# pulsegen.net
KiCad netlist of a schematic drawn in Altium Designer
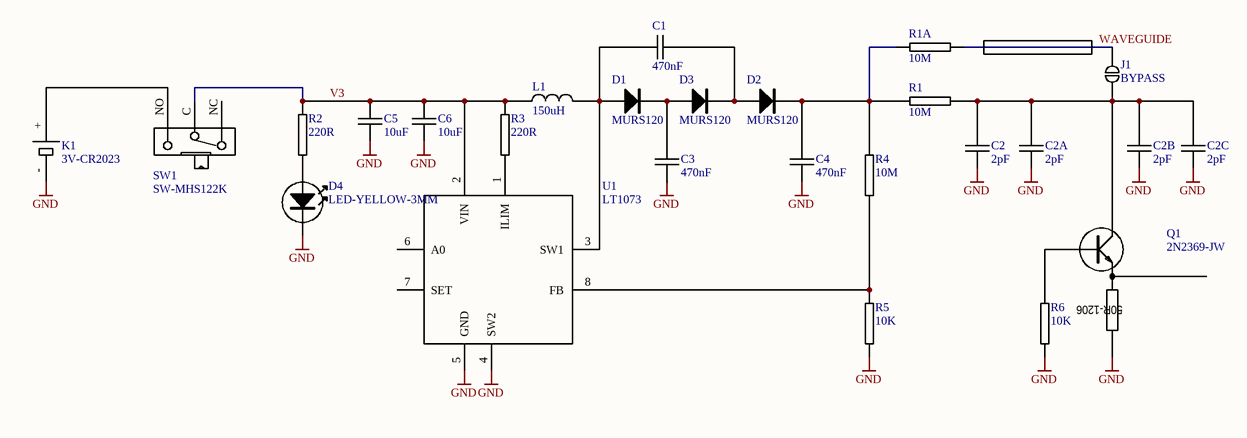
[diagram p0: pulsegen.SchDoc]

(export (version "E")
  (design (tool "Eeschema 10.0.6"))
  (components
    (comp (ref "C1")
      (value "470nF")
      (footprint "1812C-GENERIC")
      (description "CAPACITOR 1812 CERAMIC")
      (libsource (lib "SMD Capacitors Other") (part "1812C-470nF-250V-X7R-MUR"))
    )
    (comp (ref "C2")
      (value "2pF")
      (footprint "0805C-GENERIC")
      (description "CAP 10UF 6.3V CERAMIC X5R 0805")
      (fields (field (name "TOLERANCE") "±20%"))
      (libsource (lib "vh_Altium Library") (part "0805C-10UF-6V3-X5R-PAN"))
    )
    (comp (ref "C2A")
      (value "2pF")
      (footprint "0805C-GENERIC")
      (description "CAP 10UF 6.3V CERAMIC X5R 0805")
      (fields (field (name "TOLERANCE") "±20%"))
      (libsource (lib "vh_Altium Library") (part "0805C-10UF-6V3-X5R-PAN"))
    )
    (comp (ref "C2B")
      (value "2pF")
      (footprint "0805C-GENERIC")
      (description "CAP 10UF 6.3V CERAMIC X5R 0805")
      (fields (field (name "TOLERANCE") "±20%"))
      (libsource (lib "vh_Altium Library") (part "0805C-10UF-6V3-X5R-PAN"))
    )
    (comp (ref "C2C")
      (value "2pF")
      (footprint "0805C-GENERIC")
      (description "CAP 10UF 6.3V CERAMIC X5R 0805")
      (fields (field (name "TOLERANCE") "±20%"))
      (libsource (lib "vh_Altium Library") (part "0805C-10UF-6V3-X5R-PAN"))
    )
    (comp (ref "C3")
      (value "470nF")
      (footprint "1812C-GENERIC")
      (description "CAPACITOR 1812 CERAMIC")
      (libsource (lib "SMD Capacitors Other") (part "1812C-470nF-250V-X7R-MUR"))
    )
    (comp (ref "C4")
      (value "470nF")
      (footprint "1812C-GENERIC")
      (description "CAPACITOR 1812 CERAMIC")
      (libsource (lib "SMD Capacitors Other") (part "1812C-470nF-250V-X7R-MUR"))
    )
    (comp (ref "C5")
      (value "10uF")
      (footprint "0805C-GENERIC")
      (description "CAP 10UF 6.3V CERAMIC X5R 0805")
      (fields (field (name "TOLERANCE") "±20%"))
      (libsource (lib "vh_Altium Library") (part "0805C-10UF-6V3-X5R-PAN"))
    )
    (comp (ref "C6")
      (value "10uF")
      (footprint "0805C-GENERIC")
      (description "CAP 10UF 6.3V CERAMIC X5R 0805")
      (fields (field (name "TOLERANCE") "±20%"))
      (libsource (lib "vh_Altium Library") (part "0805C-10UF-6V3-X5R-PAN"))
    )
    (comp (ref "D1")
      (value "MURS120")
      (footprint "DIODE-SMB")
      (description "DIODE")
      (libsource (lib "SMD Diodes") (part "MURS120"))
    )
    (comp (ref "D2")
      (value "MURS120")
      (footprint "DIODE-SMB")
      (description "DIODE")
      (libsource (lib "SMD Diodes") (part "MURS120"))
    )
    (comp (ref "D3")
      (value "MURS120")
      (footprint "DIODE-SMB")
      (description "DIODE")
      (libsource (lib "SMD Diodes") (part "MURS120"))
    )
    (comp (ref "D4")
      (value "LED-YELLOW-3MM")
      (footprint "LED-3MM-YELLOW")
      (libsource (lib "vh_Altium Library") (part "LED-YELLOW-3MM"))
    )
    (comp (ref "J1")
      (value "BYPASS")
      (footprint "BYPASS")
      (description "Solderdot")
      (libsource (lib "vh_Altium Library") (part "BYPASS"))
    )
    (comp (ref "K1")
      (value "3V-CR2023")
      (footprint "BATCLIP-CR2032")
      (description "BU2032SM-HD-G")
      (libsource (lib "SMD Connectors") (part "BATCLIP-CR2032-SMD"))
    )
    (comp (ref "L1")
      (value "150uH")
      (footprint "TOKO-NR4018")
      (libsource (lib "SMD Magnetics") (part "150U-NR4018-TOKO"))
    )
    (comp (ref "Q1")
      (value "2N2369-JW")
      (footprint "JW2N2369")
      (libsource (lib "Specials") (part "2N2369-JW"))
    )
    (comp (ref "R1")
      (value "10M")
      (footprint "0805R-TBD")
      (description "RESISTOR 0805 VALUE TO BE DETERMINED")
      (libsource (lib "vh_Altium Library") (part "0805R-10M"))
    )
    (comp (ref "R1A")
      (value "10M")
      (footprint "0805R-TBD")
      (description "RESISTOR 0805 VALUE TO BE DETERMINED")
      (libsource (lib "vh_Altium Library") (part "0805R-10M"))
    )
    (comp (ref "R2")
      (value "220R")
      (footprint "0805R-220")
      (description "RESISTOR 0805 1/4 WATT THIN FILM")
      (libsource (lib "vh_Altium Library") (part "0805R-220"))
    )
    (comp (ref "R3")
      (value "220R")
      (footprint "0805R-220")
      (description "RESISTOR 0805 1/4 WATT THIN FILM")
      (libsource (lib "vh_Altium Library") (part "0805R-220"))
    )
    (comp (ref "R4")
      (value "10M")
      (footprint "0805R-TBD")
      (description "RESISTOR 0805 VALUE TO BE DETERMINED")
      (libsource (lib "vh_Altium Library") (part "0805R-10M"))
    )
    (comp (ref "R5")
      (value "10K")
      (footprint "0805R-10K")
      (description "RESISTOR 0805 1/4 WATT THIN FILM")
      (libsource (lib "vh_Altium Library") (part "0805R-10K"))
    )
    (comp (ref "R6")
      (value "10K")
      (footprint "0805R-10K")
      (description "RESISTOR 0805 1/4 WATT THIN FILM")
      (libsource (lib "vh_Altium Library") (part "0805R-10K"))
    )
    (comp (ref "SW1")
      (value "SW-MHS122K")
      (footprint "MHS122K")
      (description "SWITCH DPDT")
      (libsource (lib "Schlib1") (part "SW-MHS122K"))
    )
    (comp (ref "U1") (value "LT1073") (footprint "SO8") (libsource (lib "IC Regulators") (part "LT1073")))
  )
  (nets
    (net (code "1") (name "/V3") (class "Default")
      (node (ref "C5") (pin "1") (pintype "passive"))
      (node (ref "C6") (pin "1") (pintype "passive"))
      (node (ref "L1") (pin "1") (pinfunction "1_1") (pintype "passive"))
      (node (ref "R2") (pin "1") (pintype "passive"))
      (node (ref "R3") (pin "1") (pintype "passive"))
      (node (ref "SW1") (pin "C") (pintype "passive"))
      (node (ref "U1") (pin "2") (pinfunction "VIN_2") (pintype "passive"))
    )
    (net (code "2") (name "/WAVEGUIDE") (class "Default")
      (node (ref "J1") (pin "1") (pinfunction "1_1") (pintype "passive"))
      (node (ref "R1A") (pin "2") (pintype "passive"))
    )
    (net (code "3") (name "GND") (class "Default")
      (node (ref "C2") (pin "2") (pintype "passive"))
      (node (ref "C2A") (pin "2") (pintype "passive"))
      (node (ref "C2B") (pin "2") (pintype "passive"))
      (node (ref "C2C") (pin "2") (pintype "passive"))
      (node (ref "C3") (pin "1") (pintype "passive"))
      (node (ref "C4") (pin "1") (pintype "passive"))
      (node (ref "C5") (pin "2") (pintype "passive"))
      (node (ref "C6") (pin "2") (pintype "passive"))
      (node (ref "D4") (pin "K") (pintype "passive"))
      (node (ref "K1") (pin "-") (pintype "passive"))
      (node (ref "Q1") (pin "G") (pintype "passive"))
      (node (ref "R5") (pin "2") (pintype "passive"))
      (node (ref "R6") (pin "2") (pintype "passive"))
      (node (ref "U1") (pin "4") (pinfunction "SW2_4") (pintype "passive"))
      (node (ref "U1") (pin "5") (pinfunction "GND_5") (pintype "passive"))
    )
    (net (code "4") (name "Net-(C1-Pad2)") (class "Default")
      (node (ref "C1") (pin "2") (pintype "passive"))
      (node (ref "D2") (pin "A") (pinfunction "A_A") (pintype "passive"))
      (node (ref "D3") (pin "K") (pinfunction "K_K") (pintype "passive"))
    )
    (net (code "5") (name "Net-(C2-Pad1)") (class "Default")
      (node (ref "C2") (pin "1") (pintype "passive"))
      (node (ref "C2A") (pin "1") (pintype "passive"))
      (node (ref "C2B") (pin "1") (pintype "passive"))
      (node (ref "C2C") (pin "1") (pintype "passive"))
      (node (ref "J1") (pin "2") (pinfunction "2_2") (pintype "passive"))
      (node (ref "Q1") (pin "C") (pintype "passive"))
      (node (ref "R1") (pin "2") (pintype "passive"))
    )
    (net (code "6") (name "Net-(C3-Pad2)") (class "Default")
      (node (ref "C3") (pin "2") (pintype "passive"))
      (node (ref "D1") (pin "K") (pinfunction "K_K") (pintype "passive"))
      (node (ref "D3") (pin "A") (pinfunction "A_A") (pintype "passive"))
    )
    (net (code "7") (name "Net-(C4-Pad2)") (class "Default")
      (node (ref "C4") (pin "2") (pintype "passive"))
      (node (ref "D2") (pin "K") (pinfunction "K_K") (pintype "passive"))
      (node (ref "R1") (pin "1") (pintype "passive"))
      (node (ref "R1A") (pin "1") (pintype "passive"))
      (node (ref "R4") (pin "1") (pintype "passive"))
    )
    (net (code "8") (name "Net-(D4-PadA)") (class "Default")
      (node (ref "D4") (pin "A") (pintype "passive"))
      (node (ref "R2") (pin "2") (pintype "passive"))
    )
    (net (code "9") (name "Net-(K1-Pad+)") (class "Default")
      (node (ref "K1") (pin "+") (pintype "passive"))
      (node (ref "SW1") (pin "NO") (pintype "passive"))
    )
    (net (code "10") (name "Net-(Q1-PadB)") (class "Default")
      (node (ref "Q1") (pin "B") (pintype "passive"))
      (node (ref "R6") (pin "1") (pintype "passive"))
    )
    (net (code "11") (name "Net-(U1-FB)") (class "Default")
      (node (ref "R4") (pin "2") (pintype "passive"))
      (node (ref "R5") (pin "1") (pintype "passive"))
      (node (ref "U1") (pin "8") (pinfunction "FB_8") (pintype "passive"))
    )
    (net (code "12") (name "Net-(U1-ILIM)") (class "Default")
      (node (ref "R3") (pin "2") (pintype "passive"))
      (node (ref "U1") (pin "1") (pinfunction "ILIM_1") (pintype "passive"))
    )
    (net (code "13") (name "Net-(U1-SW1)") (class "Default")
      (node (ref "C1") (pin "1") (pintype "passive"))
      (node (ref "D1") (pin "A") (pinfunction "A_A") (pintype "passive"))
      (node (ref "L1") (pin "2") (pinfunction "2_2") (pintype "passive"))
      (node (ref "U1") (pin "3") (pinfunction "SW1_3") (pintype "passive"))
    )
    (net (code "14") (name "unconnected-(SW1-NC2-PadNC)") (class "Default")
      (node (ref "SW1") (pin "NC") (pinfunction "NC2_NC") (pintype "passive"))
    )
    (net (code "15") (name "unconnected-(U1-A0-Pad6)") (class "Default")
      (node (ref "U1") (pin "6") (pinfunction "A0_6") (pintype "passive"))
    )
    (net (code "16") (name "unconnected-(U1-SET-Pad7)") (class "Default")
      (node (ref "U1") (pin "7") (pinfunction "SET_7") (pintype "passive"))
    )
  )
)
